# Cookie_Synth.net
KiCad netlist of a schematic drawn in EAGLE
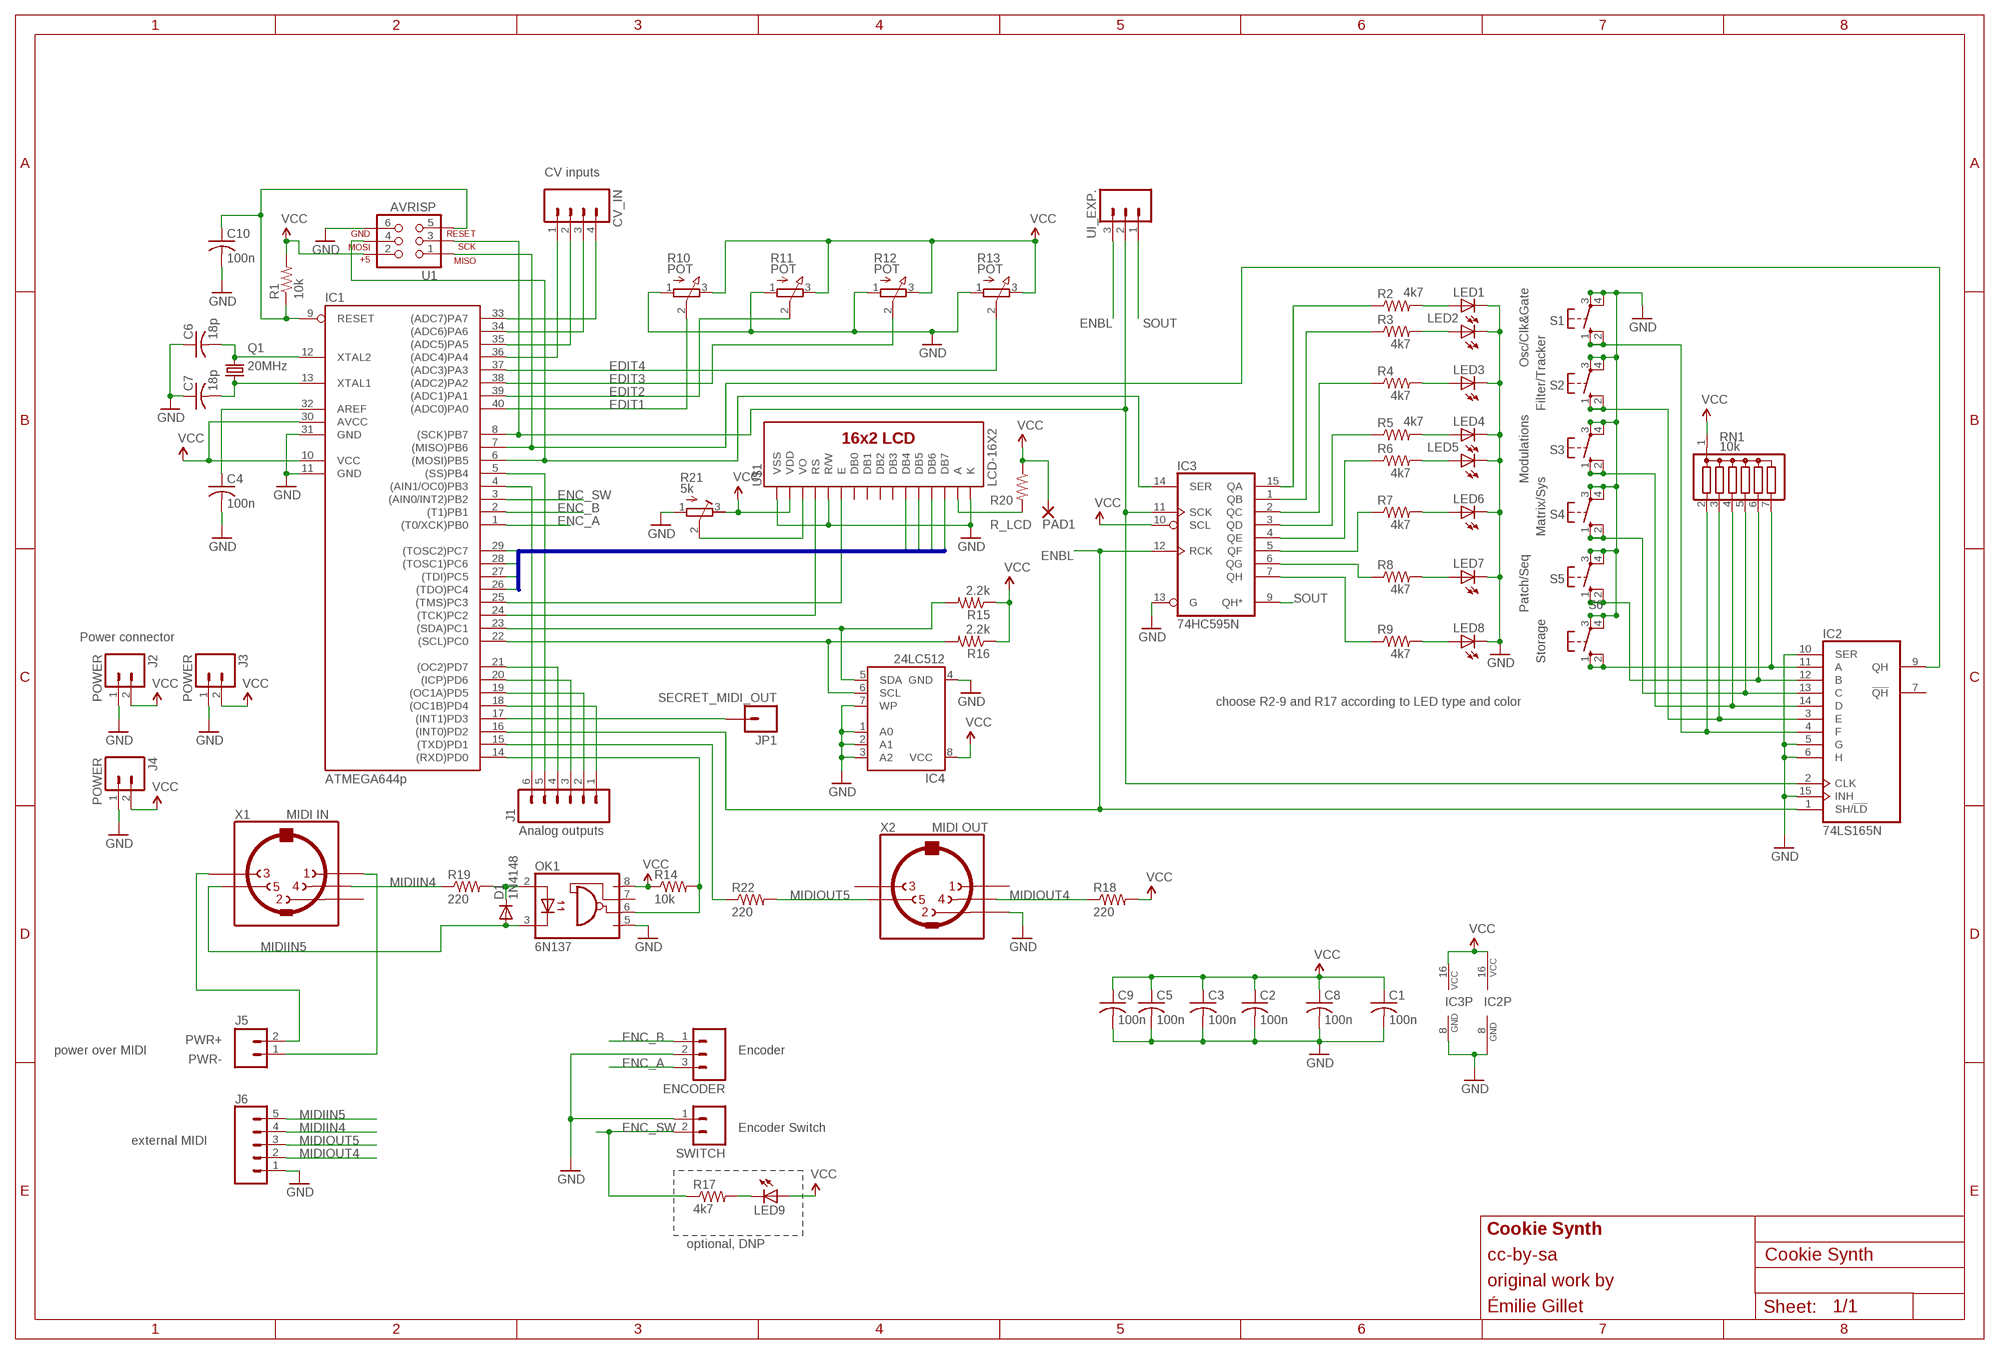
[diagram p0: schematic, sheet 1]

(export (version "E")
  (design (tool "Eeschema 10.0.6"))
  (components
    (comp (ref "C1")
      (value "100n")
      (footprint "eagle-import:C025-024X044")
      (libsource (lib "eagle-import") (part "C-US025-024X044"))
    )
    (comp (ref "C2")
      (value "100n")
      (footprint "eagle-import:C025-024X044")
      (libsource (lib "eagle-import") (part "C-US025-024X044"))
    )
    (comp (ref "C3")
      (value "100n")
      (footprint "eagle-import:C025-024X044")
      (libsource (lib "eagle-import") (part "C-US025-024X044"))
    )
    (comp (ref "C4")
      (value "100n")
      (footprint "eagle-import:C025-024X044")
      (libsource (lib "eagle-import") (part "C-US025-024X044"))
    )
    (comp (ref "C5")
      (value "100n")
      (footprint "eagle-import:C025-024X044")
      (libsource (lib "eagle-import") (part "C-US025-024X044"))
    )
    (comp (ref "C6")
      (value "18p")
      (footprint "eagle-import:C025-024X044")
      (libsource (lib "eagle-import") (part "C-US025-024X044"))
    )
    (comp (ref "C7")
      (value "18p")
      (footprint "eagle-import:C025-024X044")
      (libsource (lib "eagle-import") (part "C-US025-024X044"))
    )
    (comp (ref "C8")
      (value "100n")
      (footprint "eagle-import:C025-024X044")
      (libsource (lib "eagle-import") (part "C-US025-024X044"))
    )
    (comp (ref "C9")
      (value "100n")
      (footprint "eagle-import:C025-024X044")
      (libsource (lib "eagle-import") (part "C-US025-024X044"))
    )
    (comp (ref "C10")
      (value "100n")
      (footprint "eagle-import:C025-024X044")
      (libsource (lib "eagle-import") (part "C-US025-024X044"))
    )
    (comp (ref "CV_IN")
      (value "M04PTH")
      (footprint "eagle-import:1X04")
      (libsource (lib "eagle-import") (part "M04PTH"))
    )
    (comp (ref "D1")
      (value "1N4148")
      (footprint "eagle-import:D-5")
      (libsource (lib "eagle-import") (part "DIODE-D-5"))
    )
    (comp (ref "ENCODER")
      (value "M03PTH")
      (footprint "eagle-import:1X03")
      (libsource (lib "eagle-import") (part "M03PTH"))
    )
    (comp (ref "IC1")
      (value "ATMEGA644p")
      (footprint "eagle-import:DIL40")
      (libsource (lib "eagle-import") (part "MEGA16-P"))
    )
    (comp (ref "IC2")
      (value "74LS165N")
      (footprint "eagle-import:DIL16")
      (libsource (lib "eagle-import") (part "74165NLS"))
    )
    (comp (ref "IC3")
      (value "74HC595N")
      (footprint "eagle-import:DIL16")
      (libsource (lib "eagle-import") (part "74595NHC"))
    )
    (comp (ref "IC4")
      (value "24LC512")
      (footprint "eagle-import:DIL08")
      (libsource (lib "eagle-import") (part "AT24CP"))
    )
    (comp (ref "J1")
      (value "M06SIP")
      (footprint "eagle-import:1X06")
      (libsource (lib "eagle-import") (part "M06SIP"))
    )
    (comp (ref "J2")
      (value "POWER")
      (footprint "eagle-import:1X02")
      (libsource (lib "eagle-import") (part "M02PTH"))
    )
    (comp (ref "J3")
      (value "POWER")
      (footprint "eagle-import:1X02")
      (libsource (lib "eagle-import") (part "M02PTH"))
    )
    (comp (ref "J4")
      (value "POWER")
      (footprint "eagle-import:1X02")
      (libsource (lib "eagle-import") (part "M02PTH"))
    )
    (comp (ref "J5")
      (value "M02PTH")
      (footprint "eagle-import:1X02")
      (libsource (lib "eagle-import") (part "M02PTH"))
    )
    (comp (ref "J6")
      (value "CONN_05")
      (footprint "eagle-import:1X05")
      (libsource (lib "eagle-import") (part "CONN_05"))
    )
    (comp (ref "JP1")
      (value "SECRET_MIDI_OUT")
      (footprint "eagle-import:1X01")
      (libsource (lib "eagle-import") (part "M01PTH"))
    )
    (comp (ref "LED1")
      (value "LED3MM")
      (footprint "eagle-import:LED3MM")
      (libsource (lib "eagle-import") (part "LED3MM"))
    )
    (comp (ref "LED2")
      (value "LED3MM")
      (footprint "eagle-import:LED3MM")
      (libsource (lib "eagle-import") (part "LED3MM"))
    )
    (comp (ref "LED3")
      (value "LED3MM")
      (footprint "eagle-import:LED3MM")
      (libsource (lib "eagle-import") (part "LED3MM"))
    )
    (comp (ref "LED4")
      (value "LED3MM")
      (footprint "eagle-import:LED3MM")
      (libsource (lib "eagle-import") (part "LED3MM"))
    )
    (comp (ref "LED5")
      (value "LED3MM")
      (footprint "eagle-import:LED3MM")
      (libsource (lib "eagle-import") (part "LED3MM"))
    )
    (comp (ref "LED6")
      (value "LED3MM")
      (footprint "eagle-import:LED3MM")
      (libsource (lib "eagle-import") (part "LED3MM"))
    )
    (comp (ref "LED7")
      (value "LED3MM")
      (footprint "eagle-import:LED3MM")
      (libsource (lib "eagle-import") (part "LED3MM"))
    )
    (comp (ref "LED8")
      (value "LED3MM")
      (footprint "eagle-import:LED3MM")
      (libsource (lib "eagle-import") (part "LED3MM"))
    )
    (comp (ref "LED9")
      (value "LED3MM")
      (footprint "eagle-import:LED3MM")
      (libsource (lib "eagle-import") (part "LED3MM"))
    )
    (comp (ref "OK1")
      (value "6N137")
      (footprint "eagle-import:DIL08")
      (libsource (lib "eagle-import") (part "6N137"))
    )
    (comp (ref "PAD1")
      (value "1,6/0,8")
      (footprint "eagle-import:1,6_0,8")
      (libsource (lib "eagle-import") (part "1,6/0,8"))
    )
    (comp (ref "Q1")
      (value "20MHz")
      (footprint "eagle-import:HC49U-V")
      (libsource (lib "eagle-import") (part "CRYSTALHC49U-V"))
    )
    (comp (ref "R1")
      (value "10k")
      (footprint "eagle-import:0204_7")
      (libsource (lib "eagle-import") (part "R-US_0204/7"))
    )
    (comp (ref "R2")
      (value "4k7")
      (footprint "eagle-import:0204_7")
      (libsource (lib "eagle-import") (part "R-US_0204/7"))
    )
    (comp (ref "R3")
      (value "4k7")
      (footprint "eagle-import:0204_7")
      (libsource (lib "eagle-import") (part "R-US_0204/7"))
    )
    (comp (ref "R4")
      (value "4k7")
      (footprint "eagle-import:0204_7")
      (libsource (lib "eagle-import") (part "R-US_0204/7"))
    )
    (comp (ref "R5")
      (value "4k7")
      (footprint "eagle-import:0204_7")
      (libsource (lib "eagle-import") (part "R-US_0204/7"))
    )
    (comp (ref "R6")
      (value "4k7")
      (footprint "eagle-import:0204_7")
      (libsource (lib "eagle-import") (part "R-US_0204/7"))
    )
    (comp (ref "R7")
      (value "4k7")
      (footprint "eagle-import:0204_7")
      (libsource (lib "eagle-import") (part "R-US_0204/7"))
    )
    (comp (ref "R8")
      (value "4k7")
      (footprint "eagle-import:0204_7")
      (libsource (lib "eagle-import") (part "R-US_0204/7"))
    )
    (comp (ref "R9")
      (value "4k7")
      (footprint "eagle-import:0204_7")
      (libsource (lib "eagle-import") (part "R-US_0204/7"))
    )
    (comp (ref "R10")
      (value "POT")
      (footprint "eagle-import:POTI_ALPS_RK09")
      (libsource (lib "eagle-import") (part "POTI_ALPS_RK09"))
    )
    (comp (ref "R11")
      (value "POT")
      (footprint "eagle-import:POTI_ALPS_RK09")
      (libsource (lib "eagle-import") (part "POTI_ALPS_RK09"))
    )
    (comp (ref "R12")
      (value "POT")
      (footprint "eagle-import:POTI_ALPS_RK09")
      (libsource (lib "eagle-import") (part "POTI_ALPS_RK09"))
    )
    (comp (ref "R13")
      (value "POT")
      (footprint "eagle-import:POTI_ALPS_RK09")
      (libsource (lib "eagle-import") (part "POTI_ALPS_RK09"))
    )
    (comp (ref "R14")
      (value "10k")
      (footprint "eagle-import:0204_7")
      (libsource (lib "eagle-import") (part "R-US_0204/7"))
    )
    (comp (ref "R15")
      (value "2.2k")
      (footprint "eagle-import:0204_7")
      (libsource (lib "eagle-import") (part "R-US_0204/7"))
    )
    (comp (ref "R16")
      (value "2.2k")
      (footprint "eagle-import:0204_7")
      (libsource (lib "eagle-import") (part "R-US_0204/7"))
    )
    (comp (ref "R17")
      (value "4k7")
      (footprint "eagle-import:0204_7")
      (libsource (lib "eagle-import") (part "R-US_0204/7"))
    )
    (comp (ref "R18")
      (value "220")
      (footprint "eagle-import:0204_7")
      (libsource (lib "eagle-import") (part "R-US_0204/7"))
    )
    (comp (ref "R19")
      (value "220")
      (footprint "eagle-import:0204_7")
      (libsource (lib "eagle-import") (part "R-US_0204/7"))
    )
    (comp (ref "R20")
      (value "R_LCD")
      (footprint "eagle-import:0204_7")
      (libsource (lib "eagle-import") (part "R-US_0204/7"))
    )
    (comp (ref "R21")
      (value "5k")
      (footprint "eagle-import:RTRIM3296X")
      (libsource (lib "eagle-import") (part "R-TRIMM3296X"))
    )
    (comp (ref "R22")
      (value "220")
      (footprint "eagle-import:0204_7")
      (libsource (lib "eagle-import") (part "R-US_0204/7"))
    )
    (comp (ref "RN1")
      (value "10k")
      (footprint "eagle-import:SIL7")
      (libsource (lib "eagle-import") (part "G06R"))
    )
    (comp (ref "S1")
      (value "Osc/Clk&Gate")
      (footprint "eagle-import:B3F-40XX")
      (libsource (lib "eagle-import") (part "40-XX"))
    )
    (comp (ref "S2")
      (value "Filter/Tracker")
      (footprint "eagle-import:B3F-40XX")
      (libsource (lib "eagle-import") (part "40-XX"))
    )
    (comp (ref "S3")
      (value "Modulations")
      (footprint "eagle-import:B3F-40XX")
      (libsource (lib "eagle-import") (part "40-XX"))
    )
    (comp (ref "S4")
      (value "Matrix/Sys")
      (footprint "eagle-import:B3F-40XX")
      (libsource (lib "eagle-import") (part "40-XX"))
    )
    (comp (ref "S5")
      (value "Patch/Seq")
      (footprint "eagle-import:B3F-40XX")
      (libsource (lib "eagle-import") (part "40-XX"))
    )
    (comp (ref "S6")
      (value "Storage")
      (footprint "eagle-import:B3F-40XX")
      (libsource (lib "eagle-import") (part "40-XX"))
    )
    (comp (ref "SWITCH")
      (value "M02PTH")
      (footprint "eagle-import:1X02")
      (libsource (lib "eagle-import") (part "M02PTH"))
    )
    (comp (ref "U$1")
      (value "LCD-16X2")
      (footprint "eagle-import:LCD-16X2")
      (libsource (lib "eagle-import") (part "LCD-16X2"))
    )
    (comp (ref "U1")
      (value "AVRISP")
      (footprint "eagle-import:2X3")
      (libsource (lib "eagle-import") (part "AVR_SPI_PRG_6PTH"))
    )
    (comp (ref "UI_EXP.")
      (value "M03PTH")
      (footprint "eagle-import:1X03")
      (libsource (lib "eagle-import") (part "M03PTH"))
    )
    (comp (ref "X1")
      (value "MIDI IN")
      (footprint "eagle-import:MAB5SH")
      (libsource (lib "eagle-import") (part "MAB5SH"))
    )
    (comp (ref "X2")
      (value "MIDI OUT")
      (footprint "eagle-import:MAB5SH")
      (libsource (lib "eagle-import") (part "MAB5SH"))
    )
  )
  (nets
    (net (code "1") (name "/EDIT1") (class "Default")
      (node (ref "IC1") (pin "40") (pinfunction "(ADC0)PA0_40") (pintype "bidirectional"))
      (node (ref "R10") (pin "2") (pinfunction "S_2") (pintype "passive"))
    )
    (net (code "2") (name "/EDIT2") (class "Default")
      (node (ref "IC1") (pin "39") (pinfunction "(ADC1)PA1_39") (pintype "bidirectional"))
      (node (ref "R11") (pin "2") (pinfunction "S_2") (pintype "passive"))
    )
    (net (code "3") (name "/EDIT3") (class "Default")
      (node (ref "IC1") (pin "38") (pinfunction "(ADC2)PA2_38") (pintype "bidirectional"))
      (node (ref "R12") (pin "2") (pinfunction "S_2") (pintype "passive"))
    )
    (net (code "4") (name "/EDIT4") (class "Default")
      (node (ref "IC1") (pin "37") (pinfunction "(ADC3)PA3_37") (pintype "bidirectional"))
      (node (ref "R13") (pin "2") (pinfunction "S_2") (pintype "passive"))
    )
    (net (code "5") (name "/ENBL") (class "Default")
      (node (ref "IC1") (pin "16") (pinfunction "(INT0)PD2_16") (pintype "bidirectional"))
      (node (ref "IC2") (pin "1") (pinfunction "SH/~{LD}_1") (pintype "input"))
      (node (ref "IC3") (pin "12") (pinfunction "RCK_12") (pintype "input"))
      (node (ref "UI_EXP.") (pin "3") (pinfunction "3_3") (pintype "passive"))
    )
    (net (code "6") (name "/ENC_A") (class "Default")
      (node (ref "ENCODER") (pin "3") (pinfunction "3_3") (pintype "passive"))
      (node (ref "IC1") (pin "1") (pinfunction "(T0/XCK)PB0_1") (pintype "bidirectional"))
    )
    (net (code "7") (name "/ENC_B") (class "Default")
      (node (ref "ENCODER") (pin "1") (pinfunction "1_1") (pintype "passive"))
      (node (ref "IC1") (pin "2") (pinfunction "(T1)PB1_2") (pintype "bidirectional"))
    )
    (net (code "8") (name "/ENC_SW") (class "Default")
      (node (ref "IC1") (pin "3") (pinfunction "(AIN0/INT2)PB2_3") (pintype "bidirectional"))
      (node (ref "R17") (pin "1") (pinfunction "1_1") (pintype "passive"))
      (node (ref "SWITCH") (pin "2") (pinfunction "2_2") (pintype "passive"))
    )
    (net (code "9") (name "/LCD_DATA1") (class "Default")
      (node (ref "IC1") (pin "26") (pinfunction "(TDO)PC4_26") (pintype "bidirectional"))
      (node (ref "U$1") (pin "11") (pinfunction "DB4_11") (pintype "bidirectional"))
    )
    (net (code "10") (name "/LCD_DATA2") (class "Default")
      (node (ref "IC1") (pin "27") (pinfunction "(TDI)PC5_27") (pintype "bidirectional"))
      (node (ref "U$1") (pin "12") (pinfunction "DB5_12") (pintype "bidirectional"))
    )
    (net (code "11") (name "/LCD_DATA3") (class "Default")
      (node (ref "IC1") (pin "28") (pinfunction "(TOSC1)PC6_28") (pintype "bidirectional"))
      (node (ref "U$1") (pin "13") (pinfunction "DB6_13") (pintype "bidirectional"))
    )
    (net (code "12") (name "/LCD_DATA4") (class "Default")
      (node (ref "IC1") (pin "29") (pinfunction "(TOSC2)PC7_29") (pintype "bidirectional"))
      (node (ref "U$1") (pin "14") (pinfunction "DB7_14") (pintype "bidirectional"))
    )
    (net (code "13") (name "/MIDIIN4") (class "Default")
      (node (ref "J6") (pin "4") (pinfunction "4_4") (pintype "passive"))
      (node (ref "R19") (pin "1") (pinfunction "1_1") (pintype "passive"))
      (node (ref "X1") (pin "4") (pinfunction "4_4") (pintype "passive"))
    )
    (net (code "14") (name "/MIDIIN5") (class "Default")
      (node (ref "D1") (pin "A") (pinfunction "A_A") (pintype "passive"))
      (node (ref "J6") (pin "5") (pinfunction "5_5") (pintype "passive"))
      (node (ref "OK1") (pin "3") (pinfunction "C_3") (pintype "passive"))
      (node (ref "X1") (pin "5") (pinfunction "5_5") (pintype "passive"))
    )
    (net (code "15") (name "/MIDIOUT4") (class "Default")
      (node (ref "J6") (pin "2") (pinfunction "2_2") (pintype "passive"))
      (node (ref "R18") (pin "1") (pinfunction "1_1") (pintype "passive"))
      (node (ref "X2") (pin "4") (pinfunction "4_4") (pintype "passive"))
    )
    (net (code "16") (name "/MIDIOUT5") (class "Default")
      (node (ref "J6") (pin "3") (pinfunction "3_3") (pintype "passive"))
      (node (ref "R22") (pin "2") (pinfunction "2_2") (pintype "passive"))
      (node (ref "X2") (pin "5") (pinfunction "5_5") (pintype "passive"))
    )
    (net (code "17") (name "/SOUT") (class "Default")
      (node (ref "IC3") (pin "9") (pinfunction "QH*_9") (pintype "tri_state"))
      (node (ref "UI_EXP.") (pin "1") (pinfunction "1_1") (pintype "passive"))
    )
    (net (code "18") (name "GND") (class "Default")
      (node (ref "C1") (pin "2") (pinfunction "2_2") (pintype "passive"))
      (node (ref "C10") (pin "2") (pinfunction "2_2") (pintype "passive"))
      (node (ref "C2") (pin "2") (pinfunction "2_2") (pintype "passive"))
      (node (ref "C3") (pin "2") (pinfunction "2_2") (pintype "passive"))
      (node (ref "C4") (pin "2") (pinfunction "2_2") (pintype "passive"))
      (node (ref "C5") (pin "2") (pinfunction "2_2") (pintype "passive"))
      (node (ref "C6") (pin "1") (pinfunction "1_1") (pintype "passive"))
      (node (ref "C7") (pin "1") (pinfunction "1_1") (pintype "passive"))
      (node (ref "C8") (pin "2") (pinfunction "2_2") (pintype "passive"))
      (node (ref "C9") (pin "2") (pinfunction "2_2") (pintype "passive"))
      (node (ref "ENCODER") (pin "2") (pinfunction "2_2") (pintype "passive"))
      (node (ref "IC1") (pin "11") (pinfunction "GND_11") (pintype "power_in"))
      (node (ref "IC1") (pin "31") (pinfunction "GND_31") (pintype "power_in"))
      (node (ref "IC2") (pin "10") (pinfunction "SER_10") (pintype "input"))
      (node (ref "IC2") (pin "15") (pinfunction "INH_15") (pintype "input"))
      (node (ref "IC2") (pin "5") (pinfunction "G_5") (pintype "input"))
      (node (ref "IC2") (pin "6") (pinfunction "H_6") (pintype "input"))
      (node (ref "IC2") (pin "8") (pinfunction "GND_8") (pintype "power_in"))
      (node (ref "IC3") (pin "13") (pinfunction "G_13") (pintype "input"))
      (node (ref "IC3") (pin "8") (pinfunction "GND_8") (pintype "power_in"))
      (node (ref "IC4") (pin "1") (pinfunction "A0_1") (pintype "input"))
      (node (ref "IC4") (pin "2") (pinfunction "A1_2") (pintype "input"))
      (node (ref "IC4") (pin "3") (pinfunction "A2_3") (pintype "input"))
      (node (ref "IC4") (pin "4") (pinfunction "GND_4") (pintype "power_in"))
      (node (ref "IC4") (pin "7") (pinfunction "WP_7") (pintype "input"))
      (node (ref "J2") (pin "1") (pinfunction "1_1") (pintype "passive"))
      (node (ref "J3") (pin "1") (pinfunction "1_1") (pintype "passive"))
      (node (ref "J4") (pin "1") (pinfunction "1_1") (pintype "passive"))
      (node (ref "J6") (pin "1") (pinfunction "1_1") (pintype "passive"))
      (node (ref "LED1") (pin "K") (pinfunction "C_K") (pintype "passive"))
      (node (ref "LED2") (pin "K") (pinfunction "C_K") (pintype "passive"))
      (node (ref "LED3") (pin "K") (pinfunction "C_K") (pintype "passive"))
      (node (ref "LED4") (pin "K") (pinfunction "C_K") (pintype "passive"))
      (node (ref "LED5") (pin "K") (pinfunction "C_K") (pintype "passive"))
      (node (ref "LED6") (pin "K") (pinfunction "C_K") (pintype "passive"))
      (node (ref "LED7") (pin "K") (pinfunction "C_K") (pintype "passive"))
      (node (ref "LED8") (pin "K") (pinfunction "C_K") (pintype "passive"))
      (node (ref "OK1") (pin "5") (pinfunction "GND_5") (pintype "passive"))
      (node (ref "R10") (pin "1") (pinfunction "A_1") (pintype "passive"))
      (node (ref "R11") (pin "1") (pinfunction "A_1") (pintype "passive"))
      (node (ref "R12") (pin "1") (pinfunction "A_1") (pintype "passive"))
      (node (ref "R13") (pin "1") (pinfunction "A_1") (pintype "passive"))
      (node (ref "R21") (pin "1") (pinfunction "E_1") (pintype "passive"))
      (node (ref "S1") (pin "3") (pinfunction "P_3") (pintype "passive"))
      (node (ref "S1") (pin "4") (pinfunction "P1_4") (pintype "passive"))
      (node (ref "S2") (pin "3") (pinfunction "P_3") (pintype "passive"))
      (node (ref "S2") (pin "4") (pinfunction "P1_4") (pintype "passive"))
      (node (ref "S3") (pin "3") (pinfunction "P_3") (pintype "passive"))
      (node (ref "S3") (pin "4") (pinfunction "P1_4") (pintype "passive"))
      (node (ref "S4") (pin "3") (pinfunction "P_3") (pintype "passive"))
      (node (ref "S4") (pin "4") (pinfunction "P1_4") (pintype "passive"))
      (node (ref "S5") (pin "3") (pinfunction "P_3") (pintype "passive"))
      (node (ref "S5") (pin "4") (pinfunction "P1_4") (pintype "passive"))
      (node (ref "S6") (pin "3") (pinfunction "P_3") (pintype "passive"))
      (node (ref "S6") (pin "4") (pinfunction "P1_4") (pintype "passive"))
      (node (ref "SWITCH") (pin "1") (pinfunction "1_1") (pintype "passive"))
      (node (ref "U$1") (pin "1") (pinfunction "VSS_1") (pintype "power_in"))
      (node (ref "U$1") (pin "16") (pinfunction "K_16") (pintype "power_in"))
      (node (ref "U$1") (pin "5") (pinfunction "R/W_5") (pintype "input"))
      (node (ref "U1") (pin "6") (pinfunction "6_6") (pintype "passive"))
      (node (ref "X2") (pin "2") (pinfunction "2_2") (pintype "passive"))
    )
    (net (code "19") (name "Net-(IC1-(ADC4)PA4)") (class "Default")
      (node (ref "CV_IN") (pin "1") (pinfunction "1_1") (pintype "passive"))
      (node (ref "IC1") (pin "36") (pinfunction "(ADC4)PA4_36") (pintype "bidirectional"))
    )
    (net (code "20") (name "Net-(IC1-(ADC5)PA5)") (class "Default")
      (node (ref "CV_IN") (pin "2") (pinfunction "2_2") (pintype "passive"))
      (node (ref "IC1") (pin "35") (pinfunction "(ADC5)PA5_35") (pintype "bidirectional"))
    )
    (net (code "21") (name "Net-(IC1-(ADC6)PA6)") (class "Default")
      (node (ref "CV_IN") (pin "3") (pinfunction "3_3") (pintype "passive"))
      (node (ref "IC1") (pin "34") (pinfunction "(ADC6)PA6_34") (pintype "bidirectional"))
    )
    (net (code "22") (name "Net-(IC1-(ADC7)PA7)") (class "Default")
      (node (ref "CV_IN") (pin "4") (pinfunction "4_4") (pintype "passive"))
      (node (ref "IC1") (pin "33") (pinfunction "(ADC7)PA7_33") (pintype "bidirectional"))
    )
    (net (code "23") (name "Net-(IC1-(AIN1{slash}OC0)PB3)") (class "Default")
      (node (ref "IC1") (pin "4") (pinfunction "(AIN1/OC0)PB3_4") (pintype "bidirectional"))
      (node (ref "J1") (pin "6") (pinfunction "6_6") (pintype "passive"))
    )
    (net (code "24") (name "Net-(IC1-(ICP)PD6)") (class "Default")
      (node (ref "IC1") (pin "20") (pinfunction "(ICP)PD6_20") (pintype "bidirectional"))
      (node (ref "J1") (pin "3") (pinfunction "3_3") (pintype "passive"))
    )
    (net (code "25") (name "Net-(IC1-(INT1)PD3)") (class "Default")
      (node (ref "IC1") (pin "17") (pinfunction "(INT1)PD3_17") (pintype "bidirectional"))
      (node (ref "JP1") (pin "1") (pinfunction "1_1") (pintype "passive"))
    )
    (net (code "26") (name "Net-(IC1-(MISO)PB6)") (class "Default")
      (node (ref "IC1") (pin "7") (pinfunction "(MISO)PB6_7") (pintype "bidirectional"))
      (node (ref "IC2") (pin "9") (pinfunction "QH_9") (pintype "output"))
      (node (ref "U1") (pin "1") (pinfunction "1_1") (pintype "passive"))
    )
    (net (code "27") (name "Net-(IC1-(MOSI)PB5)") (class "Default")
      (node (ref "IC1") (pin "6") (pinfunction "(MOSI)PB5_6") (pintype "bidirectional"))
      (node (ref "IC3") (pin "14") (pinfunction "SER_14") (pintype "input"))
      (node (ref "U1") (pin "4") (pinfunction "4_4") (pintype "passive"))
    )
    (net (code "28") (name "Net-(IC1-(OC1A)PD5)") (class "Default")
      (node (ref "IC1") (pin "19") (pinfunction "(OC1A)PD5_19") (pintype "bidirectional"))
      (node (ref "J1") (pin "2") (pinfunction "2_2") (pintype "passive"))
    )
    (net (code "29") (name "Net-(IC1-(OC1B)PD4)") (class "Default")
      (node (ref "IC1") (pin "18") (pinfunction "(OC1B)PD4_18") (pintype "bidirectional"))
      (node (ref "J1") (pin "1") (pinfunction "1_1") (pintype "passive"))
    )
    (net (code "30") (name "Net-(IC1-(OC2)PD7)") (class "Default")
      (node (ref "IC1") (pin "21") (pinfunction "(OC2)PD7_21") (pintype "bidirectional"))
      (node (ref "J1") (pin "4") (pinfunction "4_4") (pintype "passive"))
    )
    (net (code "31") (name "Net-(IC1-(RXD)PD0)") (class "Default")
      (node (ref "IC1") (pin "14") (pinfunction "(RXD)PD0_14") (pintype "bidirectional"))
      (node (ref "OK1") (pin "6") (pinfunction "VO_6") (pintype "passive"))
      (node (ref "R14") (pin "2") (pinfunction "2_2") (pintype "passive"))
    )
    (net (code "32") (name "Net-(IC1-(SCK)PB7)") (class "Default")
      (node (ref "IC1") (pin "8") (pinfunction "(SCK)PB7_8") (pintype "bidirectional"))
      (node (ref "IC2") (pin "2") (pinfunction "CLK_2") (pintype "input"))
      (node (ref "IC3") (pin "11") (pinfunction "SCK_11") (pintype "input"))
      (node (ref "U1") (pin "3") (pinfunction "3_3") (pintype "passive"))
      (node (ref "UI_EXP.") (pin "2") (pinfunction "2_2") (pintype "passive"))
    )
    (net (code "33") (name "Net-(IC1-(SCL)PC0)") (class "Default")
      (node (ref "IC1") (pin "22") (pinfunction "(SCL)PC0_22") (pintype "bidirectional"))
      (node (ref "IC4") (pin "6") (pinfunction "SCL_6") (pintype "bidirectional"))
      (node (ref "R16") (pin "2") (pinfunction "2_2") (pintype "passive"))
    )
    (net (code "34") (name "Net-(IC1-(SDA)PC1)") (class "Default")
      (node (ref "IC1") (pin "23") (pinfunction "(SDA)PC1_23") (pintype "bidirectional"))
      (node (ref "IC4") (pin "5") (pinfunction "SDA_5") (pintype "bidirectional"))
      (node (ref "R15") (pin "2") (pinfunction "2_2") (pintype "passive"))
    )
    (net (code "35") (name "Net-(IC1-(SS)PB4)") (class "Default")
      (node (ref "IC1") (pin "5") (pinfunction "(SS)PB4_5") (pintype "bidirectional"))
      (node (ref "J1") (pin "5") (pinfunction "5_5") (pintype "passive"))
    )
    (net (code "36") (name "Net-(IC1-(TCK)PC2)") (class "Default")
      (node (ref "IC1") (pin "24") (pinfunction "(TCK)PC2_24") (pintype "bidirectional"))
      (node (ref "U$1") (pin "4") (pinfunction "RS_4") (pintype "input"))
    )
    (net (code "37") (name "Net-(IC1-(TMS)PC3)") (class "Default")
      (node (ref "IC1") (pin "25") (pinfunction "(TMS)PC3_25") (pintype "bidirectional"))
      (node (ref "U$1") (pin "6") (pinfunction "E_6") (pintype "input"))
    )
    (net (code "38") (name "Net-(IC1-(TXD)PD1)") (class "Default")
      (node (ref "IC1") (pin "15") (pinfunction "(TXD)PD1_15") (pintype "bidirectional"))
      (node (ref "R22") (pin "1") (pinfunction "1_1") (pintype "passive"))
    )
    (net (code "39") (name "Net-(IC1-AREF)") (class "Default")
      (node (ref "C4") (pin "1") (pinfunction "1_1") (pintype "passive"))
      (node (ref "IC1") (pin "32") (pinfunction "AREF_32") (pintype "passive"))
    )
    (net (code "40") (name "Net-(IC1-RESET)") (class "Default")
      (node (ref "C10") (pin "1") (pinfunction "1_1") (pintype "passive"))
      (node (ref "IC1") (pin "9") (pinfunction "RESET_9") (pintype "input"))
      (node (ref "R1") (pin "1") (pinfunction "1_1") (pintype "passive"))
      (node (ref "U1") (pin "5") (pinfunction "5_5") (pintype "passive"))
    )
    (net (code "41") (name "Net-(IC1-XTAL1)") (class "Default")
      (node (ref "C7") (pin "2") (pinfunction "2_2") (pintype "passive"))
      (node (ref "IC1") (pin "13") (pinfunction "XTAL1_13") (pintype "bidirectional"))
      (node (ref "Q1") (pin "1") (pinfunction "1_1") (pintype "passive"))
    )
    (net (code "42") (name "Net-(IC1-XTAL2)") (class "Default")
      (node (ref "C6") (pin "2") (pinfunction "2_2") (pintype "passive"))
      (node (ref "IC1") (pin "12") (pinfunction "XTAL2_12") (pintype "bidirectional"))
      (node (ref "Q1") (pin "2") (pinfunction "2_2") (pintype "passive"))
    )
    (net (code "43") (name "Net-(IC2A-A)") (class "Default")
      (node (ref "IC2") (pin "11") (pinfunction "A_11") (pintype "input"))
      (node (ref "RN1") (pin "7") (pinfunction "7_7") (pintype "passive"))
      (node (ref "S6") (pin "1") (pinfunction "S_1") (pintype "passive"))
      (node (ref "S6") (pin "2") (pinfunction "S1_2") (pintype "passive"))
    )
    (net (code "44") (name "Net-(IC2A-B)") (class "Default")
      (node (ref "IC2") (pin "12") (pinfunction "B_12") (pintype "input"))
      (node (ref "RN1") (pin "6") (pinfunction "6_6") (pintype "passive"))
      (node (ref "S5") (pin "1") (pinfunction "S_1") (pintype "passive"))
      (node (ref "S5") (pin "2") (pinfunction "S1_2") (pintype "passive"))
    )
    (net (code "45") (name "Net-(IC2A-C)") (class "Default")
      (node (ref "IC2") (pin "13") (pinfunction "C_13") (pintype "input"))
      (node (ref "RN1") (pin "5") (pinfunction "5_5") (pintype "passive"))
      (node (ref "S4") (pin "1") (pinfunction "S_1") (pintype "passive"))
      (node (ref "S4") (pin "2") (pinfunction "S1_2") (pintype "passive"))
    )
    (net (code "46") (name "Net-(IC2A-D)") (class "Default")
      (node (ref "IC2") (pin "14") (pinfunction "D_14") (pintype "input"))
      (node (ref "RN1") (pin "4") (pinfunction "4_4") (pintype "passive"))
      (node (ref "S3") (pin "1") (pinfunction "S_1") (pintype "passive"))
      (node (ref "S3") (pin "2") (pinfunction "S1_2") (pintype "passive"))
    )
    (net (code "47") (name "Net-(IC2A-E)") (class "Default")
      (node (ref "IC2") (pin "3") (pinfunction "E_3") (pintype "input"))
      (node (ref "RN1") (pin "3") (pinfunction "3_3") (pintype "passive"))
      (node (ref "S2") (pin "1") (pinfunction "S_1") (pintype "passive"))
      (node (ref "S2") (pin "2") (pinfunction "S1_2") (pintype "passive"))
    )
    (net (code "48") (name "Net-(IC2A-F)") (class "Default")
      (node (ref "IC2") (pin "4") (pinfunction "F_4") (pintype "input"))
      (node (ref "RN1") (pin "2") (pinfunction "2_2") (pintype "passive"))
      (node (ref "S1") (pin "1") (pinfunction "S_1") (pintype "passive"))
      (node (ref "S1") (pin "2") (pinfunction "S1_2") (pintype "passive"))
    )
    (net (code "49") (name "Net-(IC3A-QA)") (class "Default")
      (node (ref "IC3") (pin "15") (pinfunction "QA_15") (pintype "tri_state"))
      (node (ref "R2") (pin "1") (pinfunction "1_1") (pintype "passive"))
    )
    (net (code "50") (name "Net-(IC3A-QB)") (class "Default")
      (node (ref "IC3") (pin "1") (pinfunction "QB_1") (pintype "tri_state"))
      (node (ref "R3") (pin "1") (pinfunction "1_1") (pintype "passive"))
    )
    (net (code "51") (name "Net-(IC3A-QC)") (class "Default")
      (node (ref "IC3") (pin "2") (pinfunction "QC_2") (pintype "tri_state"))
      (node (ref "R4") (pin "1") (pinfunction "1_1") (pintype "passive"))
    )
    (net (code "52") (name "Net-(IC3A-QD)") (class "Default")
      (node (ref "IC3") (pin "3") (pinfunction "QD_3") (pintype "tri_state"))
      (node (ref "R5") (pin "1") (pinfunction "1_1") (pintype "passive"))
    )
    (net (code "53") (name "Net-(IC3A-QE)") (class "Default")
      (node (ref "IC3") (pin "4") (pinfunction "QE_4") (pintype "tri_state"))
      (node (ref "R6") (pin "1") (pinfunction "1_1") (pintype "passive"))
    )
    (net (code "54") (name "Net-(IC3A-QF)") (class "Default")
      (node (ref "IC3") (pin "5") (pinfunction "QF_5") (pintype "tri_state"))
      (node (ref "R7") (pin "1") (pinfunction "1_1") (pintype "passive"))
    )
    (net (code "55") (name "Net-(IC3A-QG)") (class "Default")
      (node (ref "IC3") (pin "6") (pinfunction "QG_6") (pintype "tri_state"))
      (node (ref "R8") (pin "1") (pinfunction "1_1") (pintype "passive"))
    )
    (net (code "56") (name "Net-(IC3A-QH)") (class "Default")
      (node (ref "IC3") (pin "7") (pinfunction "QH_7") (pintype "tri_state"))
      (node (ref "R9") (pin "1") (pinfunction "1_1") (pintype "passive"))
    )
    (net (code "57") (name "Net-(J5-Pad1)") (class "Default")
      (node (ref "J5") (pin "1") (pinfunction "1_1") (pintype "passive"))
      (node (ref "X1") (pin "1") (pinfunction "1_1") (pintype "passive"))
    )
    (net (code "58") (name "Net-(J5-Pad2)") (class "Default")
      (node (ref "J5") (pin "2") (pinfunction "2_2") (pintype "passive"))
      (node (ref "X1") (pin "3") (pinfunction "3_3") (pintype "passive"))
    )
    (net (code "59") (name "Net-(LED1-PadA)") (class "Default")
      (node (ref "LED1") (pin "A") (pinfunction "A_A") (pintype "passive"))
      (node (ref "R2") (pin "2") (pinfunction "2_2") (pintype "passive"))
    )
    (net (code "60") (name "Net-(LED2-PadA)") (class "Default")
      (node (ref "LED2") (pin "A") (pinfunction "A_A") (pintype "passive"))
      (node (ref "R3") (pin "2") (pinfunction "2_2") (pintype "passive"))
    )
    (net (code "61") (name "Net-(LED3-PadA)") (class "Default")
      (node (ref "LED3") (pin "A") (pinfunction "A_A") (pintype "passive"))
      (node (ref "R4") (pin "2") (pinfunction "2_2") (pintype "passive"))
    )
    (net (code "62") (name "Net-(LED4-PadA)") (class "Default")
      (node (ref "LED4") (pin "A") (pinfunction "A_A") (pintype "passive"))
      (node (ref "R5") (pin "2") (pinfunction "2_2") (pintype "passive"))
    )
    (net (code "63") (name "Net-(LED5-PadA)") (class "Default")
      (node (ref "LED5") (pin "A") (pinfunction "A_A") (pintype "passive"))
      (node (ref "R6") (pin "2") (pinfunction "2_2") (pintype "passive"))
    )
    (net (code "64") (name "Net-(LED6-PadA)") (class "Default")
      (node (ref "LED6") (pin "A") (pinfunction "A_A") (pintype "passive"))
      (node (ref "R7") (pin "2") (pinfunction "2_2") (pintype "passive"))
    )
    (net (code "65") (name "Net-(LED7-PadA)") (class "Default")
      (node (ref "LED7") (pin "A") (pinfunction "A_A") (pintype "passive"))
      (node (ref "R8") (pin "2") (pinfunction "2_2") (pintype "passive"))
    )
    (net (code "66") (name "Net-(LED8-PadA)") (class "Default")
      (node (ref "LED8") (pin "A") (pinfunction "A_A") (pintype "passive"))
      (node (ref "R9") (pin "2") (pinfunction "2_2") (pintype "passive"))
    )
    (net (code "67") (name "Net-(LED9-C)") (class "Default")
      (node (ref "LED9") (pin "K") (pinfunction "C_K") (pintype "passive"))
      (node (ref "R17") (pin "2") (pinfunction "2_2") (pintype "passive"))
    )
    (net (code "68") (name "Net-(OK1-A)") (class "Default")
      (node (ref "D1") (pin "C") (pinfunction "C_C") (pintype "passive"))
      (node (ref "OK1") (pin "2") (pinfunction "A_2") (pintype "passive"))
      (node (ref "R19") (pin "2") (pinfunction "2_2") (pintype "passive"))
    )
    (net (code "69") (name "Net-(R21-S)") (class "Default")
      (node (ref "R21") (pin "2") (pinfunction "S_2") (pintype "passive"))
      (node (ref "U$1") (pin "3") (pinfunction "VO_3") (pintype "bidirectional"))
    )
    (net (code "70") (name "Net-(U$1-A)") (class "Default")
      (node (ref "R20") (pin "2") (pinfunction "2_2") (pintype "passive"))
      (node (ref "U$1") (pin "15") (pinfunction "A_15") (pintype "power_in"))
    )
    (net (code "71") (name "VCC") (class "Default")
      (node (ref "C1") (pin "1") (pinfunction "1_1") (pintype "passive"))
      (node (ref "C2") (pin "1") (pinfunction "1_1") (pintype "passive"))
      (node (ref "C3") (pin "1") (pinfunction "1_1") (pintype "passive"))
      (node (ref "C5") (pin "1") (pinfunction "1_1") (pintype "passive"))
      (node (ref "C8") (pin "1") (pinfunction "1_1") (pintype "passive"))
      (node (ref "C9") (pin "1") (pinfunction "1_1") (pintype "passive"))
      (node (ref "IC1") (pin "10") (pinfunction "VCC_10") (pintype "power_in"))
      (node (ref "IC1") (pin "30") (pinfunction "AVCC_30") (pintype "power_in"))
      (node (ref "IC2") (pin "16") (pinfunction "VCC_16") (pintype "power_in"))
      (node (ref "IC3") (pin "10") (pinfunction "SCL_10") (pintype "input"))
      (node (ref "IC3") (pin "16") (pinfunction "VCC_16") (pintype "power_in"))
      (node (ref "IC4") (pin "8") (pinfunction "VCC_8") (pintype "power_in"))
      (node (ref "J2") (pin "2") (pinfunction "2_2") (pintype "passive"))
      (node (ref "J3") (pin "2") (pinfunction "2_2") (pintype "passive"))
      (node (ref "J4") (pin "2") (pinfunction "2_2") (pintype "passive"))
      (node (ref "LED9") (pin "A") (pinfunction "A_A") (pintype "passive"))
      (node (ref "OK1") (pin "8") (pinfunction "VCC_8") (pintype "passive"))
      (node (ref "PAD1") (pin "1") (pinfunction "P_1") (pintype "passive"))
      (node (ref "R1") (pin "2") (pinfunction "2_2") (pintype "passive"))
      (node (ref "R10") (pin "3") (pinfunction "E_3") (pintype "passive"))
      (node (ref "R11") (pin "3") (pinfunction "E_3") (pintype "passive"))
      (node (ref "R12") (pin "3") (pinfunction "E_3") (pintype "passive"))
      (node (ref "R13") (pin "3") (pinfunction "E_3") (pintype "passive"))
      (node (ref "R14") (pin "1") (pinfunction "1_1") (pintype "passive"))
      (node (ref "R15") (pin "1") (pinfunction "1_1") (pintype "passive"))
      (node (ref "R16") (pin "1") (pinfunction "1_1") (pintype "passive"))
      (node (ref "R18") (pin "2") (pinfunction "2_2") (pintype "passive"))
      (node (ref "R20") (pin "1") (pinfunction "1_1") (pintype "passive"))
      (node (ref "R21") (pin "3") (pinfunction "A_3") (pintype "passive"))
      (node (ref "RN1") (pin "1") (pinfunction "1_1") (pintype "passive"))
      (node (ref "U$1") (pin "2") (pinfunction "VDD_2") (pintype "power_in"))
      (node (ref "U1") (pin "2") (pinfunction "2_2") (pintype "passive"))
    )
    (net (code "72") (name "unconnected-(IC2A-~{QH}-Pad7)") (class "Default")
      (node (ref "IC2") (pin "7") (pinfunction "~{QH}_7") (pintype "output"))
    )
    (net (code "73") (name "unconnected-(OK1-VE-Pad7)") (class "Default")
      (node (ref "OK1") (pin "7") (pinfunction "VE_7") (pintype "passive"))
    )
    (net (code "74") (name "unconnected-(U$1-DB0-Pad7)") (class "Default")
      (node (ref "U$1") (pin "7") (pinfunction "DB0_7") (pintype "bidirectional"))
    )
    (net (code "75") (name "unconnected-(U$1-DB1-Pad8)") (class "Default")
      (node (ref "U$1") (pin "8") (pinfunction "DB1_8") (pintype "bidirectional"))
    )
    (net (code "76") (name "unconnected-(U$1-DB2-Pad9)") (class "Default")
      (node (ref "U$1") (pin "9") (pinfunction "DB2_9") (pintype "bidirectional"))
    )
    (net (code "77") (name "unconnected-(U$1-DB3-Pad10)") (class "Default")
      (node (ref "U$1") (pin "10") (pinfunction "DB3_10") (pintype "bidirectional"))
    )
    (net (code "78") (name "unconnected-(X1-Pad2)") (class "Default")
      (node (ref "X1") (pin "2") (pinfunction "2_2") (pintype "passive"))
    )
    (net (code "79") (name "unconnected-(X2-Pad1)") (class "Default")
      (node (ref "X2") (pin "1") (pinfunction "1_1") (pintype "passive"))
    )
    (net (code "80") (name "unconnected-(X2-Pad3)") (class "Default")
      (node (ref "X2") (pin "3") (pinfunction "3_3") (pintype "passive"))
    )
  )
)
